# DCDC_35V.net
KiCad netlist of a schematic drawn in Altium Designer
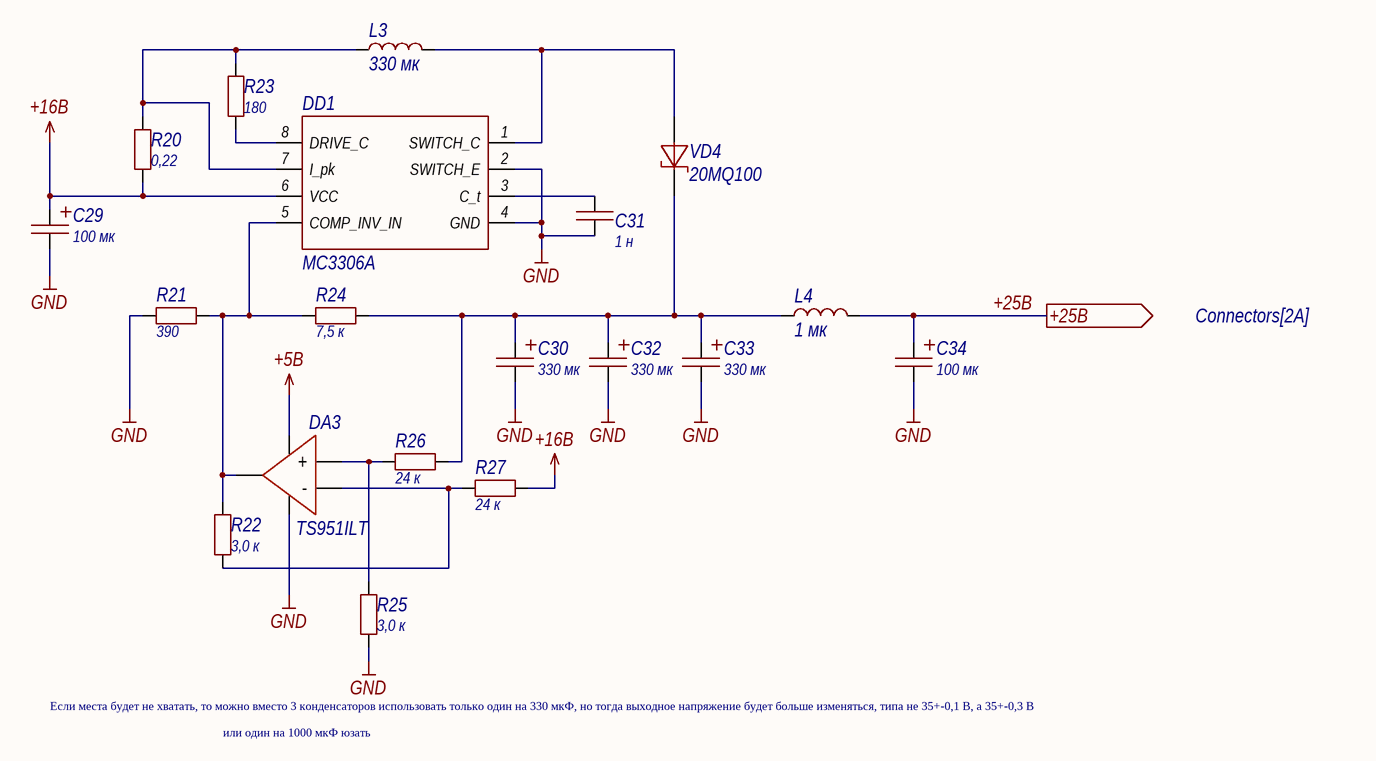
[diagram p0: DCDC_35V.SchDoc]

(export (version "E")
  (design (tool "Eeschema 10.0.6"))
  (components
    (comp (ref "C29")
      (value "100 мк")
      (footprint "ECAP_SMD_6,6x6,6")
      (description "Конденсатор алюминиевый электролитический 100мкФ 35В 20% SMD 6,6x6,6 мм")
      (fields (field (name "PART NUMBER") "JCK1V101") (field (name "TOLERANCE") "20"))
      (libsource (lib "Hydrolib") (part "Capacitor_polar"))
    )
    (comp (ref "C30")
      (value "330 мк")
      (footprint "ECAP_SMD_10,3x10,3")
      (description "Конденсатор алюминиевый электролитический 1000мкФ 25В 20% Low ESR 1100мА SMD12.5x13.5мм")
      (fields (field (name "PART NUMBER") "JCK1V331") (field (name "TOLERANCE") "20"))
      (libsource (lib "Hydrolib") (part "Capacitor_polar"))
    )
    (comp (ref "C31")
      (value "1 н")
      (footprint "0603C")
      (description "Конденсатор")
      (fields (field (name "PART NUMBER") "Capacitor_1n_10_50V_X7R_0603C") (field (name "TOLERANCE") "0,1"))
      (libsource (lib "Hydrolib") (part "Capacitor"))
    )
    (comp (ref "C32")
      (value "330 мк")
      (footprint "ECAP_SMD_10,3x10,3")
      (description "Конденсатор алюминиевый электролитический 1000мкФ 25В 20% Low ESR 1100мА SMD12.5x13.5мм")
      (fields (field (name "PART NUMBER") "JCK1V331") (field (name "TOLERANCE") "20"))
      (libsource (lib "Hydrolib") (part "Capacitor_polar"))
    )
    (comp (ref "C33")
      (value "330 мк")
      (footprint "ECAP_SMD_10,3x10,3")
      (description "Конденсатор алюминиевый электролитический 1000мкФ 25В 20% Low ESR 1100мА SMD12.5x13.5мм")
      (fields (field (name "PART NUMBER") "JCK1V331") (field (name "TOLERANCE") "20"))
      (libsource (lib "Hydrolib") (part "Capacitor_polar"))
    )
    (comp (ref "C34")
      (value "100 мк")
      (footprint "ECAP_SMD_6,6x6,6")
      (description "Конденсатор алюминиевый электролитический 100мкФ 35В 20% SMD 6,6x6,6 мм")
      (fields (field (name "PART NUMBER") "JCK1V101") (field (name "TOLERANCE") "20"))
      (libsource (lib "Hydrolib") (part "Capacitor_polar"))
    )
    (comp (ref "DA3")
      (value "TS951ILT")
      (footprint "SOt23-5")
      (description "Операционный усилитель Rail-to-Rail, 1-канальный")
      (libsource (lib "Hydrolib") (part "TS951ILT"))
    )
    (comp (ref "DD1")
      (value "MC3306A")
      (footprint "SOIC-8")
      (description "DC-DC понижающий/повышающий преобразователь, вход: 3 - 40 В, выход: 1,25 - 40 В 1,5 А")
      (libsource (lib "Hydrolib") (part "MC3306A"))
    )
    (comp (ref "L3")
      (value "330 мк")
      (footprint "12.8x12.8")
      (description "Индуктивность на 330 мкГн, номинальный ток 1,79 A")
      (fields (field (name "PART NUMBER") "CDSPRH127-331M"))
      (libsource (lib "Hydrolib") (part "Inductance"))
    )
    (comp (ref "L4")
      (value "1 мк")
      (footprint "4.5x4_wired")
      (description "Индуктивность на 1 мкГн, номинальный ток 4,3 A")
      (fields (field (name "PART NUMBER") "CDSP43-1R0M"))
      (libsource (lib "Hydrolib") (part "Inductance"))
    )
    (comp (ref "R20")
      (value "0,22")
      (footprint "2512R")
      (description "Резистор номиналом 0,22 Ом и точностью 1%")
      (fields (field (name "PART NUMBER") "Resistor_0.22_1_2512") (field (name "TOLERANCE") "1%"))
      (libsource (lib "Hydrolib") (part "Resistor"))
    )
    (comp (ref "R21")
      (value "390")
      (footprint "0603R")
      (description "Резистор номиналом 390 Ом 1%")
      (fields (field (name "PART NUMBER") "Resistor_390_1_0603") (field (name "TOLERANCE") "1%"))
      (libsource (lib "") (part "Resistor_1"))
    )
    (comp (ref "R22")
      (value "3,0 к")
      (footprint "0603R")
      (description "Резистор номиналом 3,0 кОм и точностью 1%")
      (fields (field (name "PART NUMBER") "Resistor_3.0k_1_0603") (field (name "TOLERANCE") "1%"))
      (libsource (lib "Hydrolib") (part "Resistor"))
    )
    (comp (ref "R23")
      (value "180")
      (footprint "0603R")
      (description "Резистор номиналом 180 Ом и точностью 1%")
      (fields (field (name "PART NUMBER") "Resistor_180_1_0603") (field (name "TOLERANCE") "1%"))
      (libsource (lib "") (part "Resistor_3"))
    )
    (comp (ref "R24")
      (value "7,5 к")
      (footprint "0603R")
      (description "Резистор номиналом 7,5 кОм 1%")
      (fields (field (name "PART NUMBER") "Resistor_7.5k_1_0603") (field (name "TOLERANCE") "1%"))
      (libsource (lib "") (part "Resistor_1"))
    )
    (comp (ref "R25")
      (value "3,0 к")
      (footprint "0603R")
      (description "Резистор номиналом 3,0 кОм и точностью 1%")
      (fields (field (name "PART NUMBER") "Resistor_3.0k_1_0603") (field (name "TOLERANCE") "1%"))
      (libsource (lib "Hydrolib") (part "Resistor"))
    )
    (comp (ref "R26")
      (value "24 к")
      (footprint "0603R")
      (description "Резистор номиналом 24 кОм и точностью 1%")
      (fields (field (name "PART NUMBER") "Resistor_24k_1_0603") (field (name "TOLERANCE") "1%"))
      (libsource (lib "") (part "Resistor_2"))
    )
    (comp (ref "R27")
      (value "24 к")
      (footprint "0603R")
      (description "Резистор номиналом 24 кОм и точностью 1%")
      (fields (field (name "PART NUMBER") "Resistor_24k_1_0603") (field (name "TOLERANCE") "1%"))
      (libsource (lib "") (part "Resistor_2"))
    )
    (comp (ref "VD4")
      (value "20MQ100")
      (footprint "SMA")
      (description "Диод шоттки на 100 В, ном. ток 2 А")
      (libsource (lib "Hydrolib") (part "Schottky_diode"))
    )
  )
  (nets
    (net (code "1") (name "+5В") (class "Default")
      (node (ref "DA3") (pin "5") (pinfunction "VCC_5") (pintype "passive"))
    )
    (net (code "2") (name "+16В") (class "Default")
      (node (ref "C29") (pin "1") (pinfunction "1_1") (pintype "passive"))
      (node (ref "DD1") (pin "6") (pinfunction "VCC_6") (pintype "passive"))
      (node (ref "R20") (pin "2") (pinfunction "2_2") (pintype "passive"))
      (node (ref "R27") (pin "1") (pinfunction "1_1") (pintype "passive"))
    )
    (net (code "3") (name "/+25В") (class "Default")
      (node (ref "C34") (pin "1") (pinfunction "1_1") (pintype "passive"))
      (node (ref "L4") (pin "2") (pinfunction "2_2") (pintype "passive"))
    )
    (net (code "4") (name "GND") (class "Default")
      (node (ref "C29") (pin "2") (pinfunction "2_2") (pintype "passive"))
      (node (ref "C30") (pin "2") (pinfunction "2_2") (pintype "passive"))
      (node (ref "C31") (pin "1") (pinfunction "1_1") (pintype "passive"))
      (node (ref "C32") (pin "2") (pinfunction "2_2") (pintype "passive"))
      (node (ref "C33") (pin "2") (pinfunction "2_2") (pintype "passive"))
      (node (ref "C34") (pin "2") (pinfunction "2_2") (pintype "passive"))
      (node (ref "DA3") (pin "2") (pinfunction "GND_2") (pintype "passive"))
      (node (ref "DD1") (pin "2") (pinfunction "SWITCH_E_2") (pintype "passive"))
      (node (ref "DD1") (pin "4") (pinfunction "GND_4") (pintype "passive"))
      (node (ref "R21") (pin "1") (pinfunction "1_1") (pintype "passive"))
      (node (ref "R25") (pin "2") (pinfunction "2_2") (pintype "passive"))
    )
    (net (code "5") (name "Net-(C30-Pad1)") (class "Default")
      (node (ref "C30") (pin "1") (pinfunction "1_1") (pintype "passive"))
      (node (ref "C32") (pin "1") (pinfunction "1_1") (pintype "passive"))
      (node (ref "C33") (pin "1") (pinfunction "1_1") (pintype "passive"))
      (node (ref "L4") (pin "1") (pinfunction "1_1") (pintype "passive"))
      (node (ref "R24") (pin "2") (pinfunction "2_2") (pintype "passive"))
      (node (ref "R26") (pin "1") (pinfunction "1_1") (pintype "passive"))
      (node (ref "VD4") (pin "2") (pinfunction "2_2") (pintype "passive"))
    )
    (net (code "6") (name "Net-(DA3-+)") (class "Default")
      (node (ref "DA3") (pin "3") (pinfunction "+_3") (pintype "passive"))
      (node (ref "R25") (pin "1") (pinfunction "1_1") (pintype "passive"))
      (node (ref "R26") (pin "2") (pinfunction "2_2") (pintype "passive"))
    )
    (net (code "7") (name "Net-(DA3--)") (class "Default")
      (node (ref "DA3") (pin "4") (pinfunction "-_4") (pintype "passive"))
      (node (ref "R22") (pin "2") (pinfunction "2_2") (pintype "passive"))
      (node (ref "R27") (pin "2") (pinfunction "2_2") (pintype "passive"))
    )
    (net (code "8") (name "Net-(DD1-COMP_INV_IN)") (class "Default")
      (node (ref "DA3") (pin "1") (pintype "passive"))
      (node (ref "DD1") (pin "5") (pinfunction "COMP_INV_IN_5") (pintype "passive"))
      (node (ref "R21") (pin "2") (pinfunction "2_2") (pintype "passive"))
      (node (ref "R22") (pin "1") (pinfunction "1_1") (pintype "passive"))
      (node (ref "R24") (pin "1") (pinfunction "1_1") (pintype "passive"))
    )
    (net (code "9") (name "Net-(DD1-C_t)") (class "Default")
      (node (ref "C31") (pin "2") (pinfunction "2_2") (pintype "passive"))
      (node (ref "DD1") (pin "3") (pinfunction "C_t_3") (pintype "passive"))
    )
    (net (code "10") (name "Net-(DD1-DRIVE_C)") (class "Default")
      (node (ref "DD1") (pin "8") (pinfunction "DRIVE_C_8") (pintype "passive"))
      (node (ref "R23") (pin "1") (pinfunction "1_1") (pintype "passive"))
    )
    (net (code "11") (name "Net-(DD1-I_pk)") (class "Default")
      (node (ref "DD1") (pin "7") (pinfunction "I_pk_7") (pintype "passive"))
      (node (ref "L3") (pin "1") (pinfunction "1_1") (pintype "passive"))
      (node (ref "R20") (pin "1") (pinfunction "1_1") (pintype "passive"))
      (node (ref "R23") (pin "2") (pinfunction "2_2") (pintype "passive"))
    )
    (net (code "12") (name "Net-(DD1-SWITCH_C)") (class "Default")
      (node (ref "DD1") (pin "1") (pinfunction "SWITCH_C_1") (pintype "passive"))
      (node (ref "L3") (pin "2") (pinfunction "2_2") (pintype "passive"))
      (node (ref "VD4") (pin "1") (pinfunction "1_1") (pintype "passive"))
    )
  )
)
